# schematic_rough.net
KiCad netlist of a schematic drawn in EAGLE
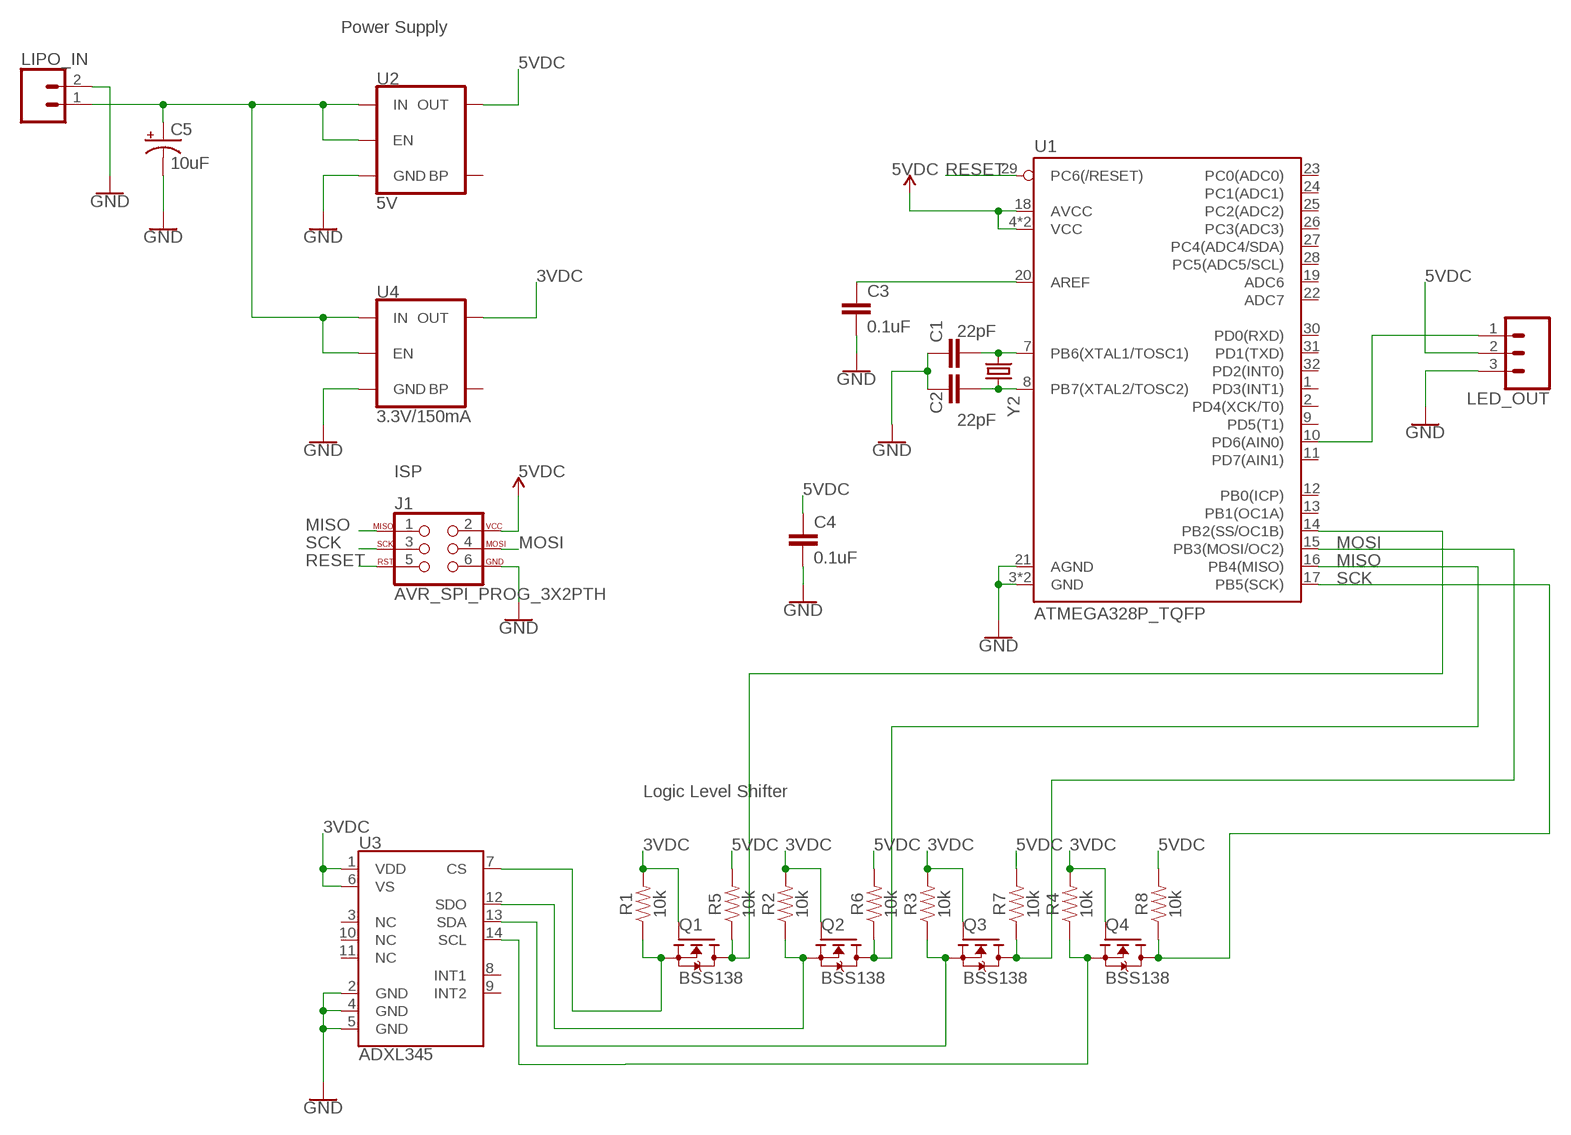
[diagram p0: schematic, sheet 1]

(export (version "E")
  (design (tool "Eeschema 10.0.6"))
  (components
    (comp (ref "C1")
      (value "22pF")
      (footprint "eagle-import:0603")
      (libsource (lib "eagle-import") (part "22PF-0603-50V-5%"))
    )
    (comp (ref "C2")
      (value "22pF")
      (footprint "eagle-import:0603")
      (libsource (lib "eagle-import") (part "22PF-0603-50V-5%"))
    )
    (comp (ref "C3")
      (value "0.1uF")
      (footprint "eagle-import:0402")
      (libsource (lib "eagle-import") (part "0.1UF-0402-16V-10%"))
    )
    (comp (ref "C4")
      (value "0.1uF")
      (footprint "eagle-import:0402")
      (libsource (lib "eagle-import") (part "0.1UF-0402-16V-10%"))
    )
    (comp (ref "C5")
      (value "10uF")
      (footprint "eagle-import:0603-POLAR")
      (libsource (lib "eagle-import") (part "10UF-POLAR-0603-6.3V-20%(TANT)"))
    )
    (comp (ref "J1")
      (value "AVR_SPI_PROG_3X2PTH")
      (footprint "eagle-import:2X3")
      (libsource (lib "eagle-import") (part "AVR_SPI_PROG_3X2PTH"))
    )
    (comp (ref "LED_OUT")
      (value "CONN_03LOCK_LONGPADS")
      (footprint "eagle-import:1X03_LOCK_LONGPADS")
      (libsource (lib "eagle-import") (part "CONN_03LOCK_LONGPADS"))
    )
    (comp (ref "LIPO_IN")
      (value "CONN_02PTH3")
      (footprint "eagle-import:1X02_LONGPADS")
      (libsource (lib "eagle-import") (part "CONN_02PTH3"))
    )
    (comp (ref "Q1")
      (value "BSS138")
      (footprint "eagle-import:SOT23")
      (fields (field (name "MF") "Fairchild"))
      (libsource (lib "eagle-import") (part "BSS138"))
    )
    (comp (ref "Q2")
      (value "BSS138")
      (footprint "eagle-import:SOT23")
      (fields (field (name "MF") "Fairchild"))
      (libsource (lib "eagle-import") (part "BSS138"))
    )
    (comp (ref "Q3")
      (value "BSS138")
      (footprint "eagle-import:SOT23")
      (fields (field (name "MF") "Fairchild"))
      (libsource (lib "eagle-import") (part "BSS138"))
    )
    (comp (ref "Q4")
      (value "BSS138")
      (footprint "eagle-import:SOT23")
      (fields (field (name "MF") "Fairchild"))
      (libsource (lib "eagle-import") (part "BSS138"))
    )
    (comp (ref "R1")
      (value "10k")
      (footprint "eagle-import:0402")
      (libsource (lib "eagle-import") (part "10KOHM-0402-1/16W-1%"))
    )
    (comp (ref "R2")
      (value "10k")
      (footprint "eagle-import:0402")
      (libsource (lib "eagle-import") (part "10KOHM-0402-1/16W-1%"))
    )
    (comp (ref "R3")
      (value "10k")
      (footprint "eagle-import:0402")
      (libsource (lib "eagle-import") (part "10KOHM-0402-1/16W-1%"))
    )
    (comp (ref "R4")
      (value "10k")
      (footprint "eagle-import:0402")
      (libsource (lib "eagle-import") (part "10KOHM-0402-1/16W-1%"))
    )
    (comp (ref "R5")
      (value "10k")
      (footprint "eagle-import:0402")
      (libsource (lib "eagle-import") (part "10KOHM-0402-1/16W-1%"))
    )
    (comp (ref "R6")
      (value "10k")
      (footprint "eagle-import:0402")
      (libsource (lib "eagle-import") (part "10KOHM-0402-1/16W-1%"))
    )
    (comp (ref "R7")
      (value "10k")
      (footprint "eagle-import:0402")
      (libsource (lib "eagle-import") (part "10KOHM-0402-1/16W-1%"))
    )
    (comp (ref "R8")
      (value "10k")
      (footprint "eagle-import:0402")
      (libsource (lib "eagle-import") (part "10KOHM-0402-1/16W-1%"))
    )
    (comp (ref "U1")
      (value "ATMEGA328P_TQFP")
      (footprint "eagle-import:TQFP32-08")
      (libsource (lib "eagle-import") (part "ATMEGA328P_TQFP"))
    )
    (comp (ref "U2")
      (value "5V")
      (footprint "eagle-import:SOT23-5")
      (libsource (lib "eagle-import") (part "V_REG_MIC52055V"))
    )
    (comp (ref "U3")
      (value "ADXL345")
      (footprint "eagle-import:LGA-14")
      (libsource (lib "eagle-import") (part "ADXL345"))
    )
    (comp (ref "U4")
      (value "3.3V/150mA")
      (footprint "eagle-import:SOT23-5")
      (libsource (lib "eagle-import") (part "V_REG_MIC52053.3V"))
    )
    (comp (ref "Y2")
      (value "CRYSTALPTH-HC49UV")
      (footprint "eagle-import:HC49U")
      (libsource (lib "eagle-import") (part "CRYSTALPTH-HC49UV"))
    )
  )
  (nets
    (net (code "1") (name "/3VDC") (class "Default")
      (node (ref "Q1") (pin "1") (pinfunction "G_1") (pintype "passive"))
      (node (ref "Q2") (pin "1") (pinfunction "G_1") (pintype "passive"))
      (node (ref "Q3") (pin "1") (pinfunction "G_1") (pintype "passive"))
      (node (ref "Q4") (pin "1") (pinfunction "G_1") (pintype "passive"))
      (node (ref "R1") (pin "2") (pinfunction "2_2") (pintype "passive"))
      (node (ref "R2") (pin "2") (pinfunction "2_2") (pintype "passive"))
      (node (ref "R3") (pin "2") (pinfunction "2_2") (pintype "passive"))
      (node (ref "R4") (pin "2") (pinfunction "2_2") (pintype "passive"))
      (node (ref "U3") (pin "1") (pinfunction "VDD_1") (pintype "bidirectional"))
      (node (ref "U3") (pin "6") (pinfunction "VS_6") (pintype "bidirectional"))
      (node (ref "U4") (pin "5") (pinfunction "OUT_5") (pintype "passive"))
    )
    (net (code "2") (name "/MISO") (class "Default")
      (node (ref "J1") (pin "1") (pinfunction "1_1") (pintype "passive"))
      (node (ref "Q2") (pin "3") (pinfunction "D_3") (pintype "passive"))
      (node (ref "R6") (pin "1") (pinfunction "1_1") (pintype "passive"))
      (node (ref "U1") (pin "16") (pinfunction "PB4(MISO)_16") (pintype "bidirectional"))
    )
    (net (code "3") (name "/MOSI") (class "Default")
      (node (ref "J1") (pin "4") (pinfunction "4_4") (pintype "passive"))
      (node (ref "Q3") (pin "3") (pinfunction "D_3") (pintype "passive"))
      (node (ref "R7") (pin "1") (pinfunction "1_1") (pintype "passive"))
      (node (ref "U1") (pin "15") (pinfunction "PB3(MOSI/OC2)_15") (pintype "bidirectional"))
    )
    (net (code "4") (name "/RESET") (class "Default")
      (node (ref "J1") (pin "5") (pinfunction "5_5") (pintype "passive"))
      (node (ref "U1") (pin "29") (pinfunction "PC6(/RESET)_29") (pintype "bidirectional"))
    )
    (net (code "5") (name "/SCK") (class "Default")
      (node (ref "J1") (pin "3") (pinfunction "3_3") (pintype "passive"))
      (node (ref "Q4") (pin "3") (pinfunction "D_3") (pintype "passive"))
      (node (ref "R8") (pin "1") (pinfunction "1_1") (pintype "passive"))
      (node (ref "U1") (pin "17") (pinfunction "PB5(SCK)_17") (pintype "bidirectional"))
    )
    (net (code "6") (name "GND") (class "Default")
      (node (ref "C1") (pin "1") (pinfunction "1_1") (pintype "passive"))
      (node (ref "C2") (pin "1") (pinfunction "1_1") (pintype "passive"))
      (node (ref "C3") (pin "2") (pinfunction "2_2") (pintype "passive"))
      (node (ref "C4") (pin "2") (pinfunction "2_2") (pintype "passive"))
      (node (ref "C5") (pin "-") (pinfunction "-_-") (pintype "passive"))
      (node (ref "J1") (pin "6") (pinfunction "6_6") (pintype "passive"))
      (node (ref "LED_OUT") (pin "3") (pinfunction "3_3") (pintype "passive"))
      (node (ref "LIPO_IN") (pin "2") (pinfunction "2_2") (pintype "passive"))
      (node (ref "U1") (pin "21") (pinfunction "AGND_21") (pintype "bidirectional"))
      (node (ref "U1") (pin "3") (pinfunction "GND_3") (pintype "bidirectional"))
      (node (ref "U1") (pin "5") (pinfunction "GND_5") (pintype "bidirectional"))
      (node (ref "U2") (pin "2") (pinfunction "GND_2") (pintype "input"))
      (node (ref "U3") (pin "2") (pinfunction "GND_2") (pintype "bidirectional"))
      (node (ref "U3") (pin "4") (pinfunction "GND_4") (pintype "bidirectional"))
      (node (ref "U3") (pin "5") (pinfunction "GND_5") (pintype "bidirectional"))
      (node (ref "U4") (pin "2") (pinfunction "GND_2") (pintype "input"))
    )
    (net (code "7") (name "Net-(Q1-D)") (class "Default")
      (node (ref "Q1") (pin "3") (pinfunction "D_3") (pintype "passive"))
      (node (ref "R5") (pin "1") (pinfunction "1_1") (pintype "passive"))
      (node (ref "U1") (pin "14") (pinfunction "PB2(SS/OC1B)_14") (pintype "bidirectional"))
    )
    (net (code "8") (name "Net-(Q1-S)") (class "Default")
      (node (ref "Q1") (pin "2") (pinfunction "S_2") (pintype "passive"))
      (node (ref "R1") (pin "1") (pinfunction "1_1") (pintype "passive"))
      (node (ref "U3") (pin "7") (pinfunction "CS_7") (pintype "bidirectional"))
    )
    (net (code "9") (name "Net-(Q2-S)") (class "Default")
      (node (ref "Q2") (pin "2") (pinfunction "S_2") (pintype "passive"))
      (node (ref "R2") (pin "1") (pinfunction "1_1") (pintype "passive"))
      (node (ref "U3") (pin "12") (pinfunction "SDO_12") (pintype "bidirectional"))
    )
    (net (code "10") (name "Net-(Q3-S)") (class "Default")
      (node (ref "Q3") (pin "2") (pinfunction "S_2") (pintype "passive"))
      (node (ref "R3") (pin "1") (pinfunction "1_1") (pintype "passive"))
      (node (ref "U3") (pin "13") (pinfunction "SDA_13") (pintype "bidirectional"))
    )
    (net (code "11") (name "Net-(Q4-S)") (class "Default")
      (node (ref "Q4") (pin "2") (pinfunction "S_2") (pintype "passive"))
      (node (ref "R4") (pin "1") (pinfunction "1_1") (pintype "passive"))
      (node (ref "U3") (pin "14") (pinfunction "SCL_14") (pintype "bidirectional"))
    )
    (net (code "12") (name "Net-(U1-AREF)") (class "Default")
      (node (ref "C3") (pin "1") (pinfunction "1_1") (pintype "passive"))
      (node (ref "U1") (pin "20") (pinfunction "AREF_20") (pintype "bidirectional"))
    )
    (net (code "13") (name "Net-(U1-PB6(XTAL1{slash}TOSC1))") (class "Default")
      (node (ref "C1") (pin "2") (pinfunction "2_2") (pintype "passive"))
      (node (ref "U1") (pin "7") (pinfunction "PB6(XTAL1/TOSC1)_7") (pintype "bidirectional"))
      (node (ref "Y2") (pin "2") (pinfunction "2_2") (pintype "passive"))
    )
    (net (code "14") (name "Net-(U1-PB7(XTAL2{slash}TOSC2))") (class "Default")
      (node (ref "C2") (pin "2") (pinfunction "2_2") (pintype "passive"))
      (node (ref "U1") (pin "8") (pinfunction "PB7(XTAL2/TOSC2)_8") (pintype "bidirectional"))
      (node (ref "Y2") (pin "1") (pinfunction "1_1") (pintype "passive"))
    )
    (net (code "15") (name "Net-(U1-PD6(AIN0))") (class "Default")
      (node (ref "LED_OUT") (pin "1") (pinfunction "1_1") (pintype "passive"))
      (node (ref "U1") (pin "10") (pinfunction "PD6(AIN0)_10") (pintype "bidirectional"))
    )
    (net (code "16") (name "Net-(U2-EN)") (class "Default")
      (node (ref "C5") (pin "+") (pinfunction "+_+") (pintype "passive"))
      (node (ref "LIPO_IN") (pin "1") (pinfunction "1_1") (pintype "passive"))
      (node (ref "U2") (pin "1") (pinfunction "IN_1") (pintype "input"))
      (node (ref "U2") (pin "3") (pinfunction "EN_3") (pintype "input"))
      (node (ref "U4") (pin "1") (pinfunction "IN_1") (pintype "input"))
      (node (ref "U4") (pin "3") (pinfunction "EN_3") (pintype "input"))
    )
    (net (code "17") (name "VCC") (class "Default")
      (node (ref "C4") (pin "1") (pinfunction "1_1") (pintype "passive"))
      (node (ref "J1") (pin "2") (pinfunction "2_2") (pintype "passive"))
      (node (ref "LED_OUT") (pin "2") (pinfunction "2_2") (pintype "passive"))
      (node (ref "R5") (pin "2") (pinfunction "2_2") (pintype "passive"))
      (node (ref "R6") (pin "2") (pinfunction "2_2") (pintype "passive"))
      (node (ref "R7") (pin "2") (pinfunction "2_2") (pintype "passive"))
      (node (ref "R8") (pin "2") (pinfunction "2_2") (pintype "passive"))
      (node (ref "U1") (pin "18") (pinfunction "AVCC_18") (pintype "bidirectional"))
      (node (ref "U1") (pin "4") (pinfunction "VCC_4") (pintype "bidirectional"))
      (node (ref "U1") (pin "6") (pinfunction "VCC_6") (pintype "bidirectional"))
      (node (ref "U2") (pin "5") (pinfunction "OUT_5") (pintype "passive"))
    )
    (net (code "18") (name "unconnected-(U1-ADC6-Pad19)") (class "Default")
      (node (ref "U1") (pin "19") (pinfunction "ADC6_19") (pintype "bidirectional"))
    )
    (net (code "19") (name "unconnected-(U1-ADC7-Pad22)") (class "Default")
      (node (ref "U1") (pin "22") (pinfunction "ADC7_22") (pintype "bidirectional"))
    )
    (net (code "20") (name "unconnected-(U1-PB0(ICP)-Pad12)") (class "Default")
      (node (ref "U1") (pin "12") (pinfunction "PB0(ICP)_12") (pintype "bidirectional"))
    )
    (net (code "21") (name "unconnected-(U1-PB1(OC1A)-Pad13)") (class "Default")
      (node (ref "U1") (pin "13") (pinfunction "PB1(OC1A)_13") (pintype "bidirectional"))
    )
    (net (code "22") (name "unconnected-(U1-PC0(ADC0)-Pad23)") (class "Default")
      (node (ref "U1") (pin "23") (pinfunction "PC0(ADC0)_23") (pintype "bidirectional"))
    )
    (net (code "23") (name "unconnected-(U1-PC1(ADC1)-Pad24)") (class "Default")
      (node (ref "U1") (pin "24") (pinfunction "PC1(ADC1)_24") (pintype "bidirectional"))
    )
    (net (code "24") (name "unconnected-(U1-PC2(ADC2)-Pad25)") (class "Default")
      (node (ref "U1") (pin "25") (pinfunction "PC2(ADC2)_25") (pintype "bidirectional"))
    )
    (net (code "25") (name "unconnected-(U1-PC3(ADC3)-Pad26)") (class "Default")
      (node (ref "U1") (pin "26") (pinfunction "PC3(ADC3)_26") (pintype "bidirectional"))
    )
    (net (code "26") (name "unconnected-(U1-PC4(ADC4{slash}SDA)-Pad27)") (class "Default")
      (node (ref "U1") (pin "27") (pinfunction "PC4(ADC4/SDA)_27") (pintype "bidirectional"))
    )
    (net (code "27") (name "unconnected-(U1-PC5(ADC5{slash}SCL)-Pad28)") (class "Default")
      (node (ref "U1") (pin "28") (pinfunction "PC5(ADC5/SCL)_28") (pintype "bidirectional"))
    )
    (net (code "28") (name "unconnected-(U1-PD0(RXD)-Pad30)") (class "Default")
      (node (ref "U1") (pin "30") (pinfunction "PD0(RXD)_30") (pintype "bidirectional"))
    )
    (net (code "29") (name "unconnected-(U1-PD1(TXD)-Pad31)") (class "Default")
      (node (ref "U1") (pin "31") (pinfunction "PD1(TXD)_31") (pintype "bidirectional"))
    )
    (net (code "30") (name "unconnected-(U1-PD2(INT0)-Pad32)") (class "Default")
      (node (ref "U1") (pin "32") (pinfunction "PD2(INT0)_32") (pintype "bidirectional"))
    )
    (net (code "31") (name "unconnected-(U1-PD3(INT1)-Pad1)") (class "Default")
      (node (ref "U1") (pin "1") (pinfunction "PD3(INT1)_1") (pintype "bidirectional"))
    )
    (net (code "32") (name "unconnected-(U1-PD4(XCK{slash}T0)-Pad2)") (class "Default")
      (node (ref "U1") (pin "2") (pinfunction "PD4(XCK/T0)_2") (pintype "bidirectional"))
    )
    (net (code "33") (name "unconnected-(U1-PD5(T1)-Pad9)") (class "Default")
      (node (ref "U1") (pin "9") (pinfunction "PD5(T1)_9") (pintype "bidirectional"))
    )
    (net (code "34") (name "unconnected-(U1-PD7(AIN1)-Pad11)") (class "Default")
      (node (ref "U1") (pin "11") (pinfunction "PD7(AIN1)_11") (pintype "bidirectional"))
    )
    (net (code "35") (name "unconnected-(U2-BP-Pad4)") (class "Default")
      (node (ref "U2") (pin "4") (pinfunction "BP_4") (pintype "input"))
    )
    (net (code "36") (name "unconnected-(U3-INT1-Pad8)") (class "Default")
      (node (ref "U3") (pin "8") (pinfunction "INT1_8") (pintype "bidirectional"))
    )
    (net (code "37") (name "unconnected-(U3-INT2-Pad9)") (class "Default")
      (node (ref "U3") (pin "9") (pinfunction "INT2_9") (pintype "bidirectional"))
    )
    (net (code "38") (name "unconnected-(U3-NC-Pad3)") (class "Default")
      (node (ref "U3") (pin "3") (pinfunction "NC_3") (pintype "bidirectional"))
    )
    (net (code "39") (name "unconnected-(U3-NC-Pad10)") (class "Default")
      (node (ref "U3") (pin "10") (pinfunction "NC_10") (pintype "bidirectional"))
    )
    (net (code "40") (name "unconnected-(U3-NC-Pad11)") (class "Default")
      (node (ref "U3") (pin "11") (pinfunction "NC_11") (pintype "bidirectional"))
    )
    (net (code "41") (name "unconnected-(U4-BP-Pad4)") (class "Default")
      (node (ref "U4") (pin "4") (pinfunction "BP_4") (pintype "input"))
    )
  )
)
